# MS5611.net
KiCad netlist of a schematic drawn in Altium Designer
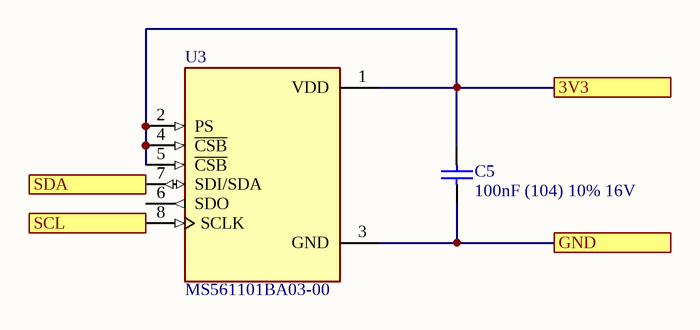
[diagram p0: MS5611.SchDoc]

(export (version "E")
  (design (tool "Eeschema 10.0.6"))
  (components
    (comp (ref "C5")
      (value "100nF (104) 10% 16V")
      (footprint "0402_C")
      (description "贴片电容")
      (libsource (lib "Miscellaneous Devices LC") (part "0402 100nF (104) 10% 16V"))
    )
    (comp (ref "U3")
      (value "MS561101BA03-00")
      (footprint "SON125P500X300X100-8N")
      (description "Pressure Sensor 1.44V to 3.6V 0.01bar to 1.2bar Absolute 8-Pin QFN Waffle Pack")
      (fields (field (name "MF") "TE Connectivity"))
      (libsource (lib "MS561101BA03-00") (part "MS561101BA03-00"))
    )
  )
  (nets
    (net (code "1") (name "/3V3") (class "Default")
      (node (ref "C5") (pin "2") (pinfunction "2_2") (pintype "passive"))
      (node (ref "U3") (pin "1") (pinfunction "VDD_1") (pintype "power_in"))
      (node (ref "U3") (pin "2") (pinfunction "PS_2") (pintype "input"))
      (node (ref "U3") (pin "4") (pinfunction "~{CSB}_4") (pintype "input"))
      (node (ref "U3") (pin "5") (pinfunction "~{CSB}_5") (pintype "input"))
    )
    (net (code "2") (name "/GND") (class "Default")
      (node (ref "C5") (pin "1") (pinfunction "1_1") (pintype "passive"))
      (node (ref "U3") (pin "3") (pinfunction "GND_3") (pintype "power_in"))
    )
    (net (code "3") (name "/SCL") (class "Default")
      (node (ref "U3") (pin "8") (pinfunction "SCLK_8") (pintype "input"))
    )
    (net (code "4") (name "/SDA") (class "Default")
      (node (ref "U3") (pin "7") (pinfunction "SDI/SDA_7") (pintype "bidirectional"))
    )
    (net (code "5") (name "unconnected-(U3-SDO-Pad6)") (class "Default")
      (node (ref "U3") (pin "6") (pinfunction "SDO_6") (pintype "output"))
    )
  )
)
